# Charge.net
KiCad netlist of a schematic drawn in Altium Designer
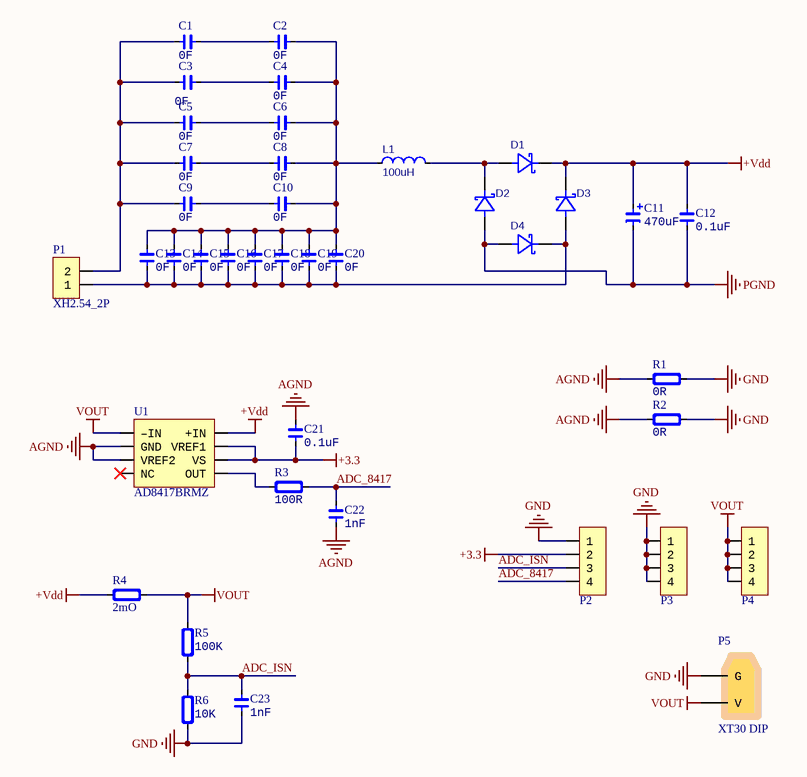
[diagram p0: Charge.SchDoc]

(export (version "E")
  (design (tool "Eeschema 10.0.6"))
  (components
    (comp (ref "C1")
      (value "0F")
      (footprint "1206_CAP")
      (description "Capacitor")
      (libsource (lib "Beacon") (part "1206_CAP"))
    )
    (comp (ref "C2")
      (value "0F")
      (footprint "1206_CAP")
      (description "Capacitor")
      (libsource (lib "Beacon") (part "1206_CAP"))
    )
    (comp (ref "C3")
      (value "0F")
      (footprint "1206_CAP")
      (description "Capacitor")
      (libsource (lib "Beacon") (part "1206_CAP"))
    )
    (comp (ref "C4")
      (value "0F")
      (footprint "1206_CAP")
      (description "Capacitor")
      (libsource (lib "Beacon") (part "1206_CAP"))
    )
    (comp (ref "C5")
      (value "0F")
      (footprint "1206_CAP")
      (description "Capacitor")
      (libsource (lib "Beacon") (part "1206_CAP"))
    )
    (comp (ref "C6")
      (value "0F")
      (footprint "1206_CAP")
      (description "Capacitor")
      (libsource (lib "Beacon") (part "1206_CAP"))
    )
    (comp (ref "C7")
      (value "0F")
      (footprint "1206_CAP")
      (description "Capacitor")
      (libsource (lib "Beacon") (part "1206_CAP"))
    )
    (comp (ref "C8")
      (value "0F")
      (footprint "1206_CAP")
      (description "Capacitor")
      (libsource (lib "Beacon") (part "1206_CAP"))
    )
    (comp (ref "C9")
      (value "0F")
      (footprint "1206_CAP")
      (description "Capacitor")
      (libsource (lib "Beacon") (part "1206_CAP"))
    )
    (comp (ref "C10")
      (value "0F")
      (footprint "1206_CAP")
      (description "Capacitor")
      (libsource (lib "Beacon") (part "1206_CAP"))
    )
    (comp (ref "C11")
      (value "470uF")
      (footprint "CAP-TH_BD8.0-P3.50-D1.0-FD")
      (description "Electrolytic capacitor")
      (libsource (lib "Beacon") (part "CAP_8x11.5"))
    )
    (comp (ref "C12")
      (value "0.1uF")
      (footprint "0805_CAP")
      (description "Capacitor")
      (libsource (lib "Beacon") (part "0805_CAP"))
    )
    (comp (ref "C13")
      (value "0F")
      (footprint "1206_CAP")
      (description "Capacitor")
      (libsource (lib "") (part "1206_CAP_1"))
    )
    (comp (ref "C14")
      (value "0F")
      (footprint "1206_CAP")
      (description "Capacitor")
      (libsource (lib "") (part "1206_CAP_1"))
    )
    (comp (ref "C15")
      (value "0F")
      (footprint "1206_CAP")
      (description "Capacitor")
      (libsource (lib "") (part "1206_CAP_1"))
    )
    (comp (ref "C16")
      (value "0F")
      (footprint "1206_CAP")
      (description "Capacitor")
      (libsource (lib "") (part "1206_CAP_1"))
    )
    (comp (ref "C17")
      (value "0F")
      (footprint "1206_CAP")
      (description "Capacitor")
      (libsource (lib "") (part "1206_CAP_1"))
    )
    (comp (ref "C18")
      (value "0F")
      (footprint "1206_CAP")
      (description "Capacitor")
      (libsource (lib "") (part "1206_CAP_1"))
    )
    (comp (ref "C19")
      (value "0F")
      (footprint "1206_CAP")
      (description "Capacitor")
      (libsource (lib "") (part "1206_CAP_1"))
    )
    (comp (ref "C20")
      (value "0F")
      (footprint "1206_CAP")
      (description "Capacitor")
      (libsource (lib "") (part "1206_CAP_1"))
    )
    (comp (ref "C21")
      (value "0.1uF")
      (footprint "0603_CAP")
      (description "Capacitor")
      (libsource (lib "Beacon") (part "0603_CAP"))
    )
    (comp (ref "C22")
      (value "1nF")
      (footprint "0603_CAP")
      (description "Capacitor")
      (libsource (lib "Beacon") (part "0603_CAP"))
    )
    (comp (ref "C23")
      (value "1nF")
      (footprint "0805_CAP")
      (description "Capacitor")
      (libsource (lib "Beacon") (part "0805_CAP"))
    )
    (comp (ref "D1")
      (value "SK86")
      (footprint "NEW footprint_2021-07-28:SMC_L7.1-W6.2-LS8.1-R-RD")
      (fields
        (field (name "BOM_SUPPLIER PART") "C698827")
        (field (name "BOM_MANUFACTURER PART") "SS86")
        (field (name "CONTRIBUTOR") "LCSC")
      )
      (libsource (lib "Beacon") (part "SK86"))
    )
    (comp (ref "D2")
      (value "SK86")
      (footprint "NEW footprint_2021-07-28:SMC_L7.1-W6.2-LS8.1-R-RD")
      (fields
        (field (name "BOM_SUPPLIER PART") "C698827")
        (field (name "BOM_MANUFACTURER PART") "SS86")
        (field (name "CONTRIBUTOR") "LCSC")
      )
      (libsource (lib "Beacon") (part "SK86"))
    )
    (comp (ref "D3")
      (value "SK86")
      (footprint "NEW footprint_2021-07-28:SMC_L7.1-W6.2-LS8.1-R-RD")
      (fields
        (field (name "BOM_SUPPLIER PART") "C698827")
        (field (name "BOM_MANUFACTURER PART") "SS86")
        (field (name "CONTRIBUTOR") "LCSC")
      )
      (libsource (lib "Beacon") (part "SK86"))
    )
    (comp (ref "D4")
      (value "SK86")
      (footprint "NEW footprint_2021-07-28:SMC_L7.1-W6.2-LS8.1-R-RD")
      (fields
        (field (name "BOM_SUPPLIER PART") "C698827")
        (field (name "BOM_MANUFACTURER PART") "SS86")
        (field (name "CONTRIBUTOR") "LCSC")
      )
      (libsource (lib "Beacon") (part "SK86"))
    )
    (comp (ref "L1")
      (value "100uH")
      (footprint "Winding inductance")
      (description "Inductor")
      (fields
        (field (name "BOM_SUPPLIER PART") "C696490")
        (field (name "BOM_MANUFACTURER PART") "MPIT6045-330M-LF")
        (field (name "CONTRIBUTOR") "LCSC")
      )
      (libsource (lib "Beacon") (part "IND"))
    )
    (comp (ref "P1")
      (value "XH2.54_2P")
      (footprint "XH2.54_2P")
      (libsource (lib "Beacon") (part "XH2.54_2P"))
    )
    (comp (ref "P2")
      (value "HDR1x4_2.54")
      (footprint "HDR_1X4")
      (description "Header")
      (libsource (lib "Beacon") (part "HDR1x4_2.54"))
    )
    (comp (ref "P3")
      (value "HDR1x4_2.54")
      (footprint "HDR_1X4")
      (description "Header")
      (libsource (lib "Beacon") (part "HDR1x4_2.54"))
    )
    (comp (ref "P4")
      (value "HDR1x4_2.54")
      (footprint "HDR_1X4")
      (description "Header")
      (libsource (lib "Beacon") (part "HDR1x4_2.54"))
    )
    (comp (ref "P5")
      (value "XT30 DIP")
      (footprint "XT30 DIP")
      (description "XT30 板载直头直插")
      (libsource (lib "Beacon") (part "XT30 DIP"))
    )
    (comp (ref "R1")
      (value "0R")
      (footprint "0805_RES")
      (description "Resistor")
      (libsource (lib "Beacon") (part "0805_RES"))
    )
    (comp (ref "R2")
      (value "0R")
      (footprint "0805_RES")
      (description "Resistor")
      (libsource (lib "Beacon") (part "0805_RES"))
    )
    (comp (ref "R3")
      (value "100R")
      (footprint "0603_RES")
      (description "Resistor")
      (libsource (lib "Beacon") (part "0603_RES"))
    )
    (comp (ref "R4")
      (value "2mO")
      (footprint "2512_RES")
      (description "Resistor")
      (libsource (lib "car bottom") (part "2512_RES"))
    )
    (comp (ref "R5")
      (value "100K")
      (footprint "0805_RES")
      (description "Resistor")
      (libsource (lib "Beacon") (part "0805_RES"))
    )
    (comp (ref "R6")
      (value "10K")
      (footprint "0805_RES")
      (description "Resistor")
      (libsource (lib "Beacon") (part "0805_RES"))
    )
    (comp (ref "U1")
      (value "AD8417BRMZ")
      (footprint "MSOP-8_L3.0-W3.0-P0.65-LS4.9-BL")
      (libsource (lib "Beacon") (part "AD8417BRMZ"))
    )
  )
  (nets
    (net (code "1") (name "+3.3") (class "Default")
      (node (ref "C21") (pin "1") (pinfunction "1_1") (pintype "passive"))
      (node (ref "P2") (pin "2") (pinfunction "2_2") (pintype "passive"))
      (node (ref "U1") (pin "6") (pinfunction "VS_6") (pintype "passive"))
      (node (ref "U1") (pin "7") (pinfunction "VREF1_7") (pintype "passive"))
    )
    (net (code "2") (name "+Vdd") (class "Default")
      (node (ref "C11") (pin "1") (pinfunction "1_1") (pintype "passive"))
      (node (ref "C12") (pin "2") (pinfunction "2_2") (pintype "passive"))
      (node (ref "D1") (pin "2") (pinfunction "2_2") (pintype "passive"))
      (node (ref "D3") (pin "2") (pinfunction "2_2") (pintype "passive"))
      (node (ref "R4") (pin "1") (pinfunction "1_1") (pintype "passive"))
      (node (ref "U1") (pin "8") (pinfunction "+IN_8") (pintype "passive"))
    )
    (net (code "3") (name "/ADC_8417") (class "Default")
      (node (ref "C22") (pin "2") (pinfunction "2_2") (pintype "passive"))
      (node (ref "P2") (pin "4") (pinfunction "4_4") (pintype "passive"))
      (node (ref "R3") (pin "2") (pinfunction "2_2") (pintype "passive"))
    )
    (net (code "4") (name "/ADC_ISN") (class "Default")
      (node (ref "C23") (pin "2") (pinfunction "2_2") (pintype "passive"))
      (node (ref "P2") (pin "3") (pinfunction "3_3") (pintype "passive"))
      (node (ref "R5") (pin "1") (pinfunction "1_1") (pintype "passive"))
      (node (ref "R6") (pin "2") (pinfunction "2_2") (pintype "passive"))
    )
    (net (code "5") (name "AGND") (class "Default")
      (node (ref "C21") (pin "2") (pinfunction "2_2") (pintype "passive"))
      (node (ref "C22") (pin "1") (pinfunction "1_1") (pintype "passive"))
      (node (ref "R1") (pin "1") (pinfunction "1_1") (pintype "passive"))
      (node (ref "R2") (pin "1") (pinfunction "1_1") (pintype "passive"))
      (node (ref "U1") (pin "2") (pinfunction "GND_2") (pintype "passive"))
      (node (ref "U1") (pin "3") (pinfunction "VREF2_3") (pintype "passive"))
    )
    (net (code "6") (name "GND") (class "Default")
      (node (ref "C23") (pin "1") (pinfunction "1_1") (pintype "passive"))
      (node (ref "P2") (pin "1") (pinfunction "1_1") (pintype "passive"))
      (node (ref "P3") (pin "1") (pinfunction "1_1") (pintype "passive"))
      (node (ref "P3") (pin "2") (pinfunction "2_2") (pintype "passive"))
      (node (ref "P3") (pin "3") (pinfunction "3_3") (pintype "passive"))
      (node (ref "P3") (pin "4") (pinfunction "4_4") (pintype "passive"))
      (node (ref "P5") (pin "2") (pinfunction "G_2") (pintype "passive"))
      (node (ref "R1") (pin "2") (pinfunction "2_2") (pintype "passive"))
      (node (ref "R2") (pin "2") (pinfunction "2_2") (pintype "passive"))
      (node (ref "R6") (pin "1") (pinfunction "1_1") (pintype "passive"))
    )
    (net (code "7") (name "Net-(C1-Pad1)") (class "Default")
      (node (ref "C1") (pin "1") (pinfunction "1_1") (pintype "passive"))
      (node (ref "C3") (pin "1") (pinfunction "1_1") (pintype "passive"))
      (node (ref "C5") (pin "1") (pinfunction "1_1") (pintype "passive"))
      (node (ref "C7") (pin "1") (pinfunction "1_1") (pintype "passive"))
      (node (ref "C9") (pin "1") (pinfunction "1_1") (pintype "passive"))
      (node (ref "P1") (pin "2") (pinfunction "2_2") (pintype "passive"))
    )
    (net (code "8") (name "Net-(C1-Pad2)") (class "Default")
      (node (ref "C1") (pin "2") (pinfunction "2_2") (pintype "passive"))
      (node (ref "C2") (pin "1") (pinfunction "1_1") (pintype "passive"))
    )
    (net (code "9") (name "Net-(C3-Pad2)") (class "Default")
      (node (ref "C3") (pin "2") (pinfunction "2_2") (pintype "passive"))
      (node (ref "C4") (pin "1") (pinfunction "1_1") (pintype "passive"))
    )
    (net (code "10") (name "Net-(C5-Pad2)") (class "Default")
      (node (ref "C5") (pin "2") (pinfunction "2_2") (pintype "passive"))
      (node (ref "C6") (pin "1") (pinfunction "1_1") (pintype "passive"))
    )
    (net (code "11") (name "Net-(C7-Pad2)") (class "Default")
      (node (ref "C7") (pin "2") (pinfunction "2_2") (pintype "passive"))
      (node (ref "C8") (pin "1") (pinfunction "1_1") (pintype "passive"))
    )
    (net (code "12") (name "Net-(C10-Pad1)") (class "Default")
      (node (ref "C10") (pin "1") (pinfunction "1_1") (pintype "passive"))
      (node (ref "C9") (pin "2") (pinfunction "2_2") (pintype "passive"))
    )
    (net (code "13") (name "Net-(C10-Pad2)") (class "Default")
      (node (ref "C10") (pin "2") (pinfunction "2_2") (pintype "passive"))
      (node (ref "C13") (pin "2") (pinfunction "2_2") (pintype "passive"))
      (node (ref "C14") (pin "2") (pinfunction "2_2") (pintype "passive"))
      (node (ref "C15") (pin "2") (pinfunction "2_2") (pintype "passive"))
      (node (ref "C16") (pin "2") (pinfunction "2_2") (pintype "passive"))
      (node (ref "C17") (pin "2") (pinfunction "2_2") (pintype "passive"))
      (node (ref "C18") (pin "2") (pinfunction "2_2") (pintype "passive"))
      (node (ref "C19") (pin "2") (pinfunction "2_2") (pintype "passive"))
      (node (ref "C2") (pin "2") (pinfunction "2_2") (pintype "passive"))
      (node (ref "C20") (pin "2") (pinfunction "2_2") (pintype "passive"))
      (node (ref "C4") (pin "2") (pinfunction "2_2") (pintype "passive"))
      (node (ref "C6") (pin "2") (pinfunction "2_2") (pintype "passive"))
      (node (ref "C8") (pin "2") (pinfunction "2_2") (pintype "passive"))
      (node (ref "L1") (pin "1") (pinfunction "1_1") (pintype "passive"))
    )
    (net (code "14") (name "Net-(C13-Pad1)") (class "Default")
      (node (ref "C13") (pin "1") (pinfunction "1_1") (pintype "passive"))
      (node (ref "C14") (pin "1") (pinfunction "1_1") (pintype "passive"))
      (node (ref "C15") (pin "1") (pinfunction "1_1") (pintype "passive"))
      (node (ref "C16") (pin "1") (pinfunction "1_1") (pintype "passive"))
      (node (ref "C17") (pin "1") (pinfunction "1_1") (pintype "passive"))
      (node (ref "C18") (pin "1") (pinfunction "1_1") (pintype "passive"))
      (node (ref "C19") (pin "1") (pinfunction "1_1") (pintype "passive"))
      (node (ref "C20") (pin "1") (pinfunction "1_1") (pintype "passive"))
      (node (ref "D3") (pin "1") (pinfunction "1_1") (pintype "passive"))
      (node (ref "D4") (pin "2") (pinfunction "2_2") (pintype "passive"))
      (node (ref "P1") (pin "1") (pinfunction "1_1") (pintype "passive"))
    )
    (net (code "15") (name "Net-(D1-Pad1)") (class "Default")
      (node (ref "D1") (pin "1") (pinfunction "1_1") (pintype "passive"))
      (node (ref "D2") (pin "2") (pinfunction "2_2") (pintype "passive"))
      (node (ref "L1") (pin "2") (pinfunction "2_2") (pintype "passive"))
    )
    (net (code "16") (name "Net-(U1-OUT)") (class "Default")
      (node (ref "R3") (pin "1") (pinfunction "1_1") (pintype "passive"))
      (node (ref "U1") (pin "5") (pinfunction "OUT_5") (pintype "passive"))
    )
    (net (code "17") (name "PGND") (class "Default")
      (node (ref "C11") (pin "2") (pinfunction "2_2") (pintype "passive"))
      (node (ref "C12") (pin "1") (pinfunction "1_1") (pintype "passive"))
      (node (ref "D2") (pin "1") (pinfunction "1_1") (pintype "passive"))
      (node (ref "D4") (pin "1") (pinfunction "1_1") (pintype "passive"))
    )
    (net (code "18") (name "VOUT") (class "Default")
      (node (ref "P4") (pin "1") (pinfunction "1_1") (pintype "passive"))
      (node (ref "P4") (pin "2") (pinfunction "2_2") (pintype "passive"))
      (node (ref "P4") (pin "3") (pinfunction "3_3") (pintype "passive"))
      (node (ref "P4") (pin "4") (pinfunction "4_4") (pintype "passive"))
      (node (ref "P5") (pin "1") (pinfunction "V_1") (pintype "passive"))
      (node (ref "R4") (pin "2") (pinfunction "2_2") (pintype "passive"))
      (node (ref "R5") (pin "2") (pinfunction "2_2") (pintype "passive"))
      (node (ref "U1") (pin "1") (pinfunction "–IN_1") (pintype "passive"))
    )
    (net (code "19") (name "unconnected-(U1-NC-Pad4)") (class "Default")
      (node (ref "U1") (pin "4") (pinfunction "NC_4") (pintype "passive+no_connect"))
    )
  )
)
